# TH.net
KiCad netlist of a schematic drawn in EAGLE
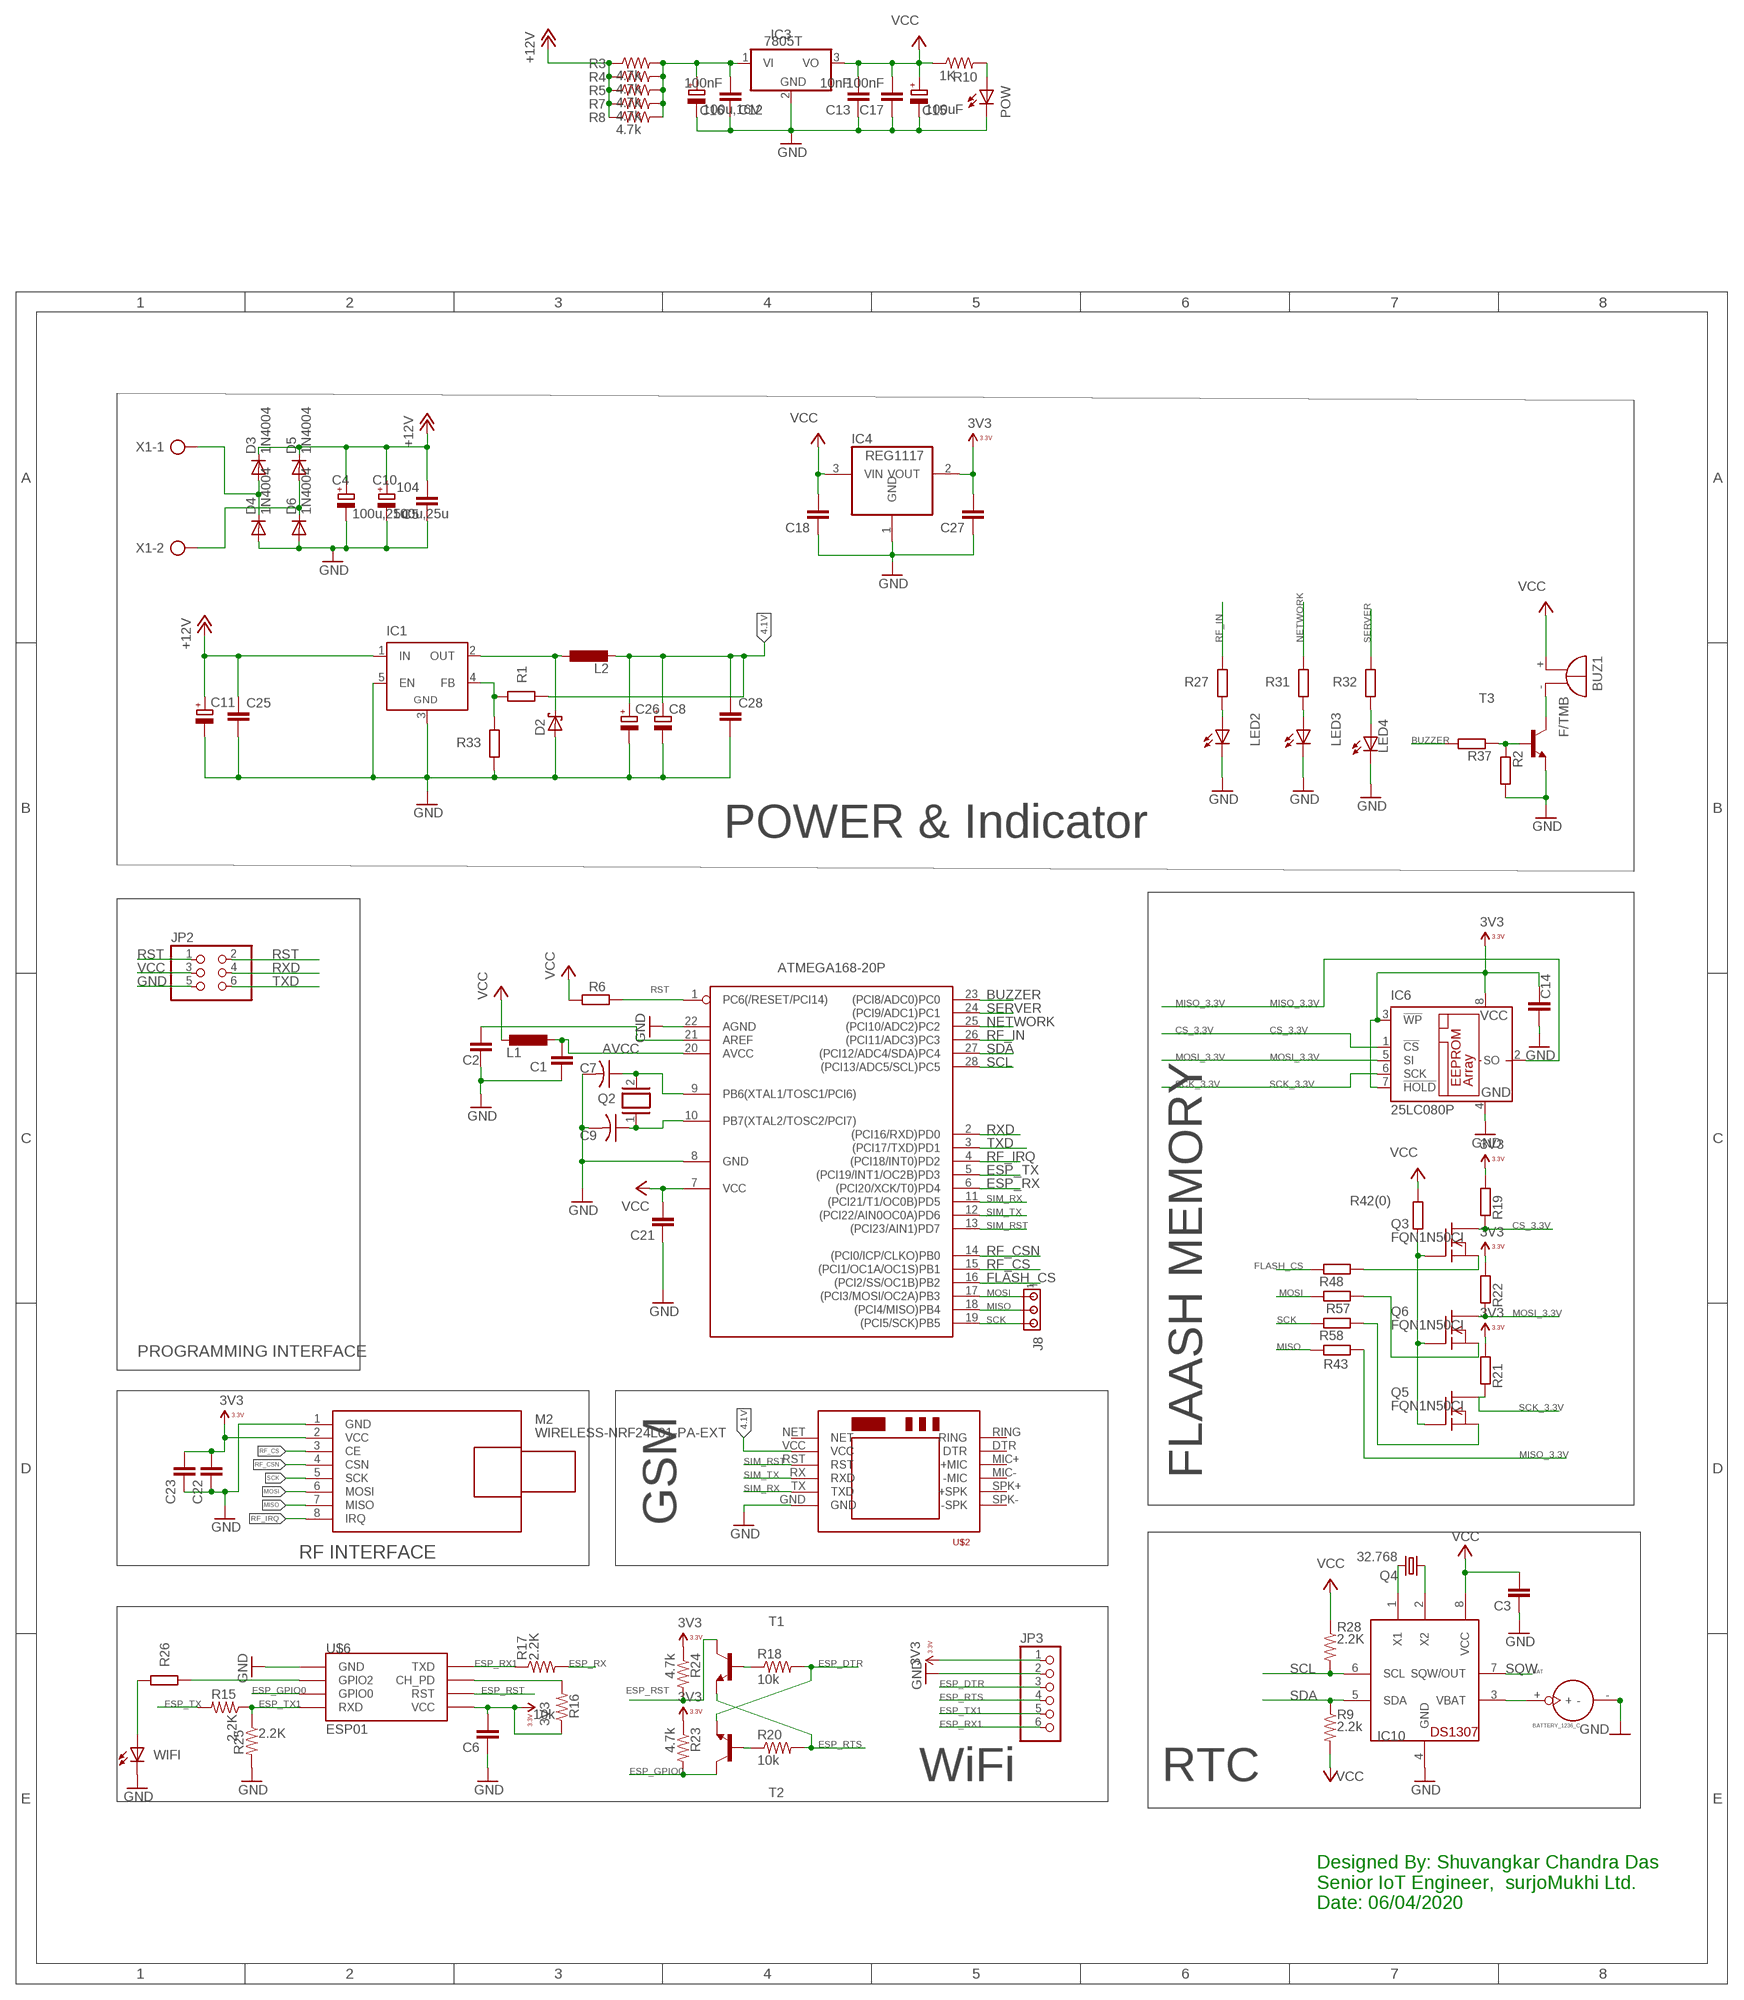
[diagram p0: schematic, sheet 1]

(export (version "E")
  (design (tool "Eeschema 10.0.6"))
  (components
    (comp (ref "BAT")
      (value "BATTERY_1236_C")
      (footprint "eagle-import:BATTERY_1236_C")
      (libsource (lib "eagle-import") (part "BATTERY_1236_C"))
    )
    (comp (ref "BUZ1")
      (value "F/TMB")
      (footprint "eagle-import:F_TMB")
      (libsource (lib "eagle-import") (part "F/TMB"))
    )
    (comp (ref "C1")
      (value "C-EU050-024X044")
      (footprint "eagle-import:C050-024X044")
      (libsource (lib "eagle-import") (part "C-EU050-024X044"))
    )
    (comp (ref "C2")
      (value "C-EU025-025X050")
      (footprint "eagle-import:C025-025X050")
      (libsource (lib "eagle-import") (part "C-EU025-025X050"))
    )
    (comp (ref "C3")
      (value "C-EU050-024X044")
      (footprint "eagle-import:C050-024X044")
      (libsource (lib "eagle-import") (part "C-EU050-024X044"))
    )
    (comp (ref "C4")
      (value "100u,25u")
      (footprint "eagle-import:E3,5-10")
      (libsource (lib "eagle-import") (part "CPOL-EUE3.5-10"))
    )
    (comp (ref "C5")
      (value "104")
      (footprint "eagle-import:C050-024X044")
      (libsource (lib "eagle-import") (part "C-EU050-024X044"))
    )
    (comp (ref "C6")
      (value "C-EU050-024X044")
      (footprint "eagle-import:C050-024X044")
      (libsource (lib "eagle-import") (part "C-EU050-024X044"))
    )
    (comp (ref "C7")
      (value "C-US050-024X044")
      (footprint "eagle-import:C050-024X044")
      (libsource (lib "eagle-import") (part "C-US050-024X044"))
    )
    (comp (ref "C8")
      (value "CPOL-EUE2.5-7")
      (footprint "eagle-import:E2,5-7")
      (libsource (lib "eagle-import") (part "resistor_CPOL-EUE2.5-7"))
    )
    (comp (ref "C9")
      (value "C-US050-024X044")
      (footprint "eagle-import:C050-024X044")
      (libsource (lib "eagle-import") (part "C-US050-024X044"))
    )
    (comp (ref "C10")
      (value "100u,25u")
      (footprint "eagle-import:E3,5-10")
      (libsource (lib "eagle-import") (part "CPOL-EUE3.5-10"))
    )
    (comp (ref "C11")
      (value "CPOL-EUE2.5-7")
      (footprint "eagle-import:E2,5-7")
      (libsource (lib "eagle-import") (part "resistor_CPOL-EUE2.5-7"))
    )
    (comp (ref "C12")
      (value "100nF")
      (footprint "eagle-import:C050-024X044")
      (libsource (lib "eagle-import") (part "C-EU050-024X044"))
    )
    (comp (ref "C13")
      (value "10nF")
      (footprint "eagle-import:C050-024X044")
      (libsource (lib "eagle-import") (part "C-EU050-024X044"))
    )
    (comp (ref "C14")
      (value "C-EU050-024X044")
      (footprint "eagle-import:C050-024X044")
      (libsource (lib "eagle-import") (part "C-EU050-024X044"))
    )
    (comp (ref "C15")
      (value "100uF")
      (footprint "eagle-import:TT2D6")
      (libsource (lib "eagle-import") (part "CPOL-EUTT2D6"))
    )
    (comp (ref "C16")
      (value "100u,16V")
      (footprint "eagle-import:TT2D6")
      (libsource (lib "eagle-import") (part "CPOL-EUTT2D6"))
    )
    (comp (ref "C17")
      (value "100nF")
      (footprint "eagle-import:C050-024X044")
      (libsource (lib "eagle-import") (part "C-EU050-024X044"))
    )
    (comp (ref "C18")
      (value "C-EU050-024X044")
      (footprint "eagle-import:C050-024X044")
      (libsource (lib "eagle-import") (part "C-EU050-024X044"))
    )
    (comp (ref "C21")
      (value "C-EU050-024X044")
      (footprint "eagle-import:C050-024X044")
      (libsource (lib "eagle-import") (part "C-EU050-024X044"))
    )
    (comp (ref "C22")
      (value "C-EU050-024X044")
      (footprint "eagle-import:C050-024X044")
      (libsource (lib "eagle-import") (part "C-EU050-024X044"))
    )
    (comp (ref "C23")
      (value "C-EU050-024X044")
      (footprint "eagle-import:C050-024X044")
      (libsource (lib "eagle-import") (part "C-EU050-024X044"))
    )
    (comp (ref "C25")
      (value "C-EU050-024X044")
      (footprint "eagle-import:C050-024X044")
      (libsource (lib "eagle-import") (part "resistor_C-EU050-024X044"))
    )
    (comp (ref "C26")
      (value "CPOL-EUE2.5-7")
      (footprint "eagle-import:E2,5-7")
      (libsource (lib "eagle-import") (part "resistor_CPOL-EUE2.5-7"))
    )
    (comp (ref "C27")
      (value "C-EU050-024X044")
      (footprint "eagle-import:C050-024X044")
      (libsource (lib "eagle-import") (part "C-EU050-024X044"))
    )
    (comp (ref "C28")
      (value "C-EU050-024X044")
      (footprint "eagle-import:C050-024X044")
      (libsource (lib "eagle-import") (part "resistor_C-EU050-024X044"))
    )
    (comp (ref "D2")
      (value "SCHOTTKY-DIODEDO41")
      (footprint "eagle-import:DO41-10")
      (libsource (lib "eagle-import") (part "SCHOTTKY-DIODEDO41"))
    )
    (comp (ref "D3")
      (value "1N4004")
      (footprint "eagle-import:DO41-10")
      (libsource (lib "eagle-import") (part "1N4004"))
    )
    (comp (ref "D4")
      (value "1N4004")
      (footprint "eagle-import:DO41-10")
      (libsource (lib "eagle-import") (part "1N4004"))
    )
    (comp (ref "D5")
      (value "1N4004")
      (footprint "eagle-import:DO41-10")
      (libsource (lib "eagle-import") (part "1N4004"))
    )
    (comp (ref "D6")
      (value "1N4004")
      (footprint "eagle-import:DO41-10")
      (libsource (lib "eagle-import") (part "1N4004"))
    )
    (comp (ref "IC1")
      (value "LM2596TH")
      (footprint "eagle-import:TO220-52")
      (libsource (lib "eagle-import") (part "LM2596TH"))
    )
    (comp (ref "IC3")
      (value "7805T")
      (footprint "eagle-import:TO220H")
      (libsource (lib "eagle-import") (part "78T05"))
    )
    (comp (ref "IC4")
      (value "REG1117")
      (footprint "eagle-import:SOT223")
      (libsource (lib "eagle-import") (part "REG1117"))
    )
    (comp (ref "IC6")
      (value "25LC080P")
      (footprint "eagle-import:DIL8")
      (fields (field (name "MF") "MICROCHIP") (field (name "MPN") "25LC080/P"))
      (libsource (lib "eagle-import") (part "25PLC080"))
    )
    (comp (ref "IC7")
      (value "ATMEGA168-20P")
      (footprint "eagle-import:DIL28-3")
      (libsource (lib "eagle-import") (part "ATMEGA168P-20"))
    )
    (comp (ref "IC10")
      (value "DS1307")
      (footprint "eagle-import:DIL08")
      (libsource (lib "eagle-import") (part "DS1307"))
    )
    (comp (ref "J8")
      (value "MTA03-100")
      (footprint "eagle-import:10X03MTA")
      (libsource (lib "eagle-import") (part "MTA03-100"))
    )
    (comp (ref "JP2")
      (value "PINHD-2X3")
      (footprint "eagle-import:2X03")
      (libsource (lib "eagle-import") (part "PINHD-2X3"))
    )
    (comp (ref "JP3")
      (value "PINHD-1X6")
      (footprint "eagle-import:1X06")
      (libsource (lib "eagle-import") (part "PINHD-1X6"))
    )
    (comp (ref "L1")
      (value "L-EU0207/15")
      (footprint "eagle-import:0207_15")
      (libsource (lib "eagle-import") (part "L-EU0207/15"))
    )
    (comp (ref "L2")
      (value "L-EU0207/10")
      (footprint "eagle-import:0207_10")
      (libsource (lib "eagle-import") (part "L-EU0207/10"))
    )
    (comp (ref "LED2")
      (value "LED3MM")
      (footprint "eagle-import:LED3MM")
      (libsource (lib "eagle-import") (part "LED3MM"))
    )
    (comp (ref "LED3")
      (value "LED3MM")
      (footprint "eagle-import:LED3MM")
      (libsource (lib "eagle-import") (part "LED3MM"))
    )
    (comp (ref "LED4")
      (value "LED3MM")
      (footprint "eagle-import:LED3MM")
      (libsource (lib "eagle-import") (part "LED3MM"))
    )
    (comp (ref "M2")
      (value "WIRELESS-NRF24L01-PA-EXT")
      (footprint "eagle-import:WIRELESS-NRF24L01-PA-EXT")
      (libsource (lib "eagle-import") (part "WIRELESS-NRF24L01-PA-EXT"))
    )
    (comp (ref "POW")
      (value "LED3MM")
      (footprint "eagle-import:LED3MM")
      (libsource (lib "eagle-import") (part "LED3MM"))
    )
    (comp (ref "Q2")
      (value "XTAL/S")
      (footprint "eagle-import:QS")
      (libsource (lib "eagle-import") (part "XTAL/S"))
    )
    (comp (ref "Q3")
      (value "FQN1N50CI")
      (footprint "eagle-import:TO92-INLINE")
      (libsource (lib "eagle-import") (part "FQN1N50CI"))
    )
    (comp (ref "Q4")
      (value "32.768")
      (footprint "eagle-import:TC38H")
      (libsource (lib "eagle-import") (part "CRYTALTC38H"))
    )
    (comp (ref "Q5")
      (value "FQN1N50CI")
      (footprint "eagle-import:TO92-INLINE")
      (libsource (lib "eagle-import") (part "FQN1N50CI"))
    )
    (comp (ref "Q6")
      (value "FQN1N50CI")
      (footprint "eagle-import:TO92-INLINE")
      (libsource (lib "eagle-import") (part "FQN1N50CI"))
    )
    (comp (ref "R1")
      (value "R-EU_0204/7")
      (footprint "eagle-import:0204_7")
      (libsource (lib "eagle-import") (part "R-EU_0204/7"))
    )
    (comp (ref "R2")
      (value "R-EU_0204/7")
      (footprint "eagle-import:0204_7")
      (libsource (lib "eagle-import") (part "R-EU_0204/7"))
    )
    (comp (ref "R3")
      (value "4.7k")
      (footprint "eagle-import:0204_7")
      (libsource (lib "eagle-import") (part "R-US_0204/7"))
    )
    (comp (ref "R4")
      (value "4.7k")
      (footprint "eagle-import:0204_7")
      (libsource (lib "eagle-import") (part "R-US_0204/7"))
    )
    (comp (ref "R5")
      (value "4.7k")
      (footprint "eagle-import:0204_7")
      (libsource (lib "eagle-import") (part "R-US_0204/7"))
    )
    (comp (ref "R6")
      (value "R-EU_0204/7")
      (footprint "eagle-import:0204_7")
      (libsource (lib "eagle-import") (part "R-EU_0204/7"))
    )
    (comp (ref "R7")
      (value "4.7k")
      (footprint "eagle-import:0204_7")
      (libsource (lib "eagle-import") (part "R-US_0204/7"))
    )
    (comp (ref "R8")
      (value "4.7k")
      (footprint "eagle-import:0204_7")
      (libsource (lib "eagle-import") (part "R-US_0204/7"))
    )
    (comp (ref "R9")
      (value "2.2k")
      (footprint "eagle-import:0204_7")
      (libsource (lib "eagle-import") (part "R-US_0204/7"))
    )
    (comp (ref "R10")
      (value "1K")
      (footprint "eagle-import:0204_7")
      (libsource (lib "eagle-import") (part "R-US_0204/7"))
    )
    (comp (ref "R15")
      (value "2.2K")
      (footprint "eagle-import:0204_7")
      (libsource (lib "eagle-import") (part "R-US_0204/7"))
    )
    (comp (ref "R16")
      (value "10k")
      (footprint "eagle-import:0204_7")
      (libsource (lib "eagle-import") (part "R-US_0204/7"))
    )
    (comp (ref "R17")
      (value "2.2K")
      (footprint "eagle-import:0204_7")
      (libsource (lib "eagle-import") (part "R-US_0204/7"))
    )
    (comp (ref "R18")
      (value "10k")
      (footprint "eagle-import:0204_7")
      (libsource (lib "eagle-import") (part "R-US_0204/7"))
    )
    (comp (ref "R19")
      (value "R-EU_0204/7")
      (footprint "eagle-import:0204_7")
      (libsource (lib "eagle-import") (part "R-EU_0204/7"))
    )
    (comp (ref "R20")
      (value "10k")
      (footprint "eagle-import:0204_7")
      (libsource (lib "eagle-import") (part "R-US_0204/7"))
    )
    (comp (ref "R21")
      (value "R-EU_0204/7")
      (footprint "eagle-import:0204_7")
      (libsource (lib "eagle-import") (part "R-EU_0204/7"))
    )
    (comp (ref "R22")
      (value "R-EU_0204/7")
      (footprint "eagle-import:0204_7")
      (libsource (lib "eagle-import") (part "R-EU_0204/7"))
    )
    (comp (ref "R23")
      (value "4.7k")
      (footprint "eagle-import:0204_7")
      (libsource (lib "eagle-import") (part "R-US_0204/7"))
    )
    (comp (ref "R24")
      (value "4.7k")
      (footprint "eagle-import:0204_7")
      (libsource (lib "eagle-import") (part "R-US_0204/7"))
    )
    (comp (ref "R25")
      (value "2.2K")
      (footprint "eagle-import:0204_7")
      (libsource (lib "eagle-import") (part "R-US_0204/7"))
    )
    (comp (ref "R26")
      (value "R-EU_0204/7")
      (footprint "eagle-import:0204_7")
      (libsource (lib "eagle-import") (part "R-EU_0204/7"))
    )
    (comp (ref "R27")
      (value "R-EU_0207/10")
      (footprint "eagle-import:0207_10")
      (libsource (lib "eagle-import") (part "R-EU_0207/10"))
    )
    (comp (ref "R28")
      (value "2.2K")
      (footprint "eagle-import:0204_7")
      (libsource (lib "eagle-import") (part "R-US_0204/7"))
    )
    (comp (ref "R31")
      (value "R-EU_0207/10")
      (footprint "eagle-import:0207_10")
      (libsource (lib "eagle-import") (part "R-EU_0207/10"))
    )
    (comp (ref "R32")
      (value "R-EU_0207/10")
      (footprint "eagle-import:0207_10")
      (libsource (lib "eagle-import") (part "R-EU_0207/10"))
    )
    (comp (ref "R33")
      (value "R-EU_0204/7")
      (footprint "eagle-import:0204_7")
      (libsource (lib "eagle-import") (part "R-EU_0204/7"))
    )
    (comp (ref "R37")
      (value "R-EU_0204/7")
      (footprint "eagle-import:0204_7")
      (libsource (lib "eagle-import") (part "R-EU_0204/7"))
    )
    (comp (ref "R42(0)")
      (value "R-EU_0207/10")
      (footprint "eagle-import:0207_10")
      (libsource (lib "eagle-import") (part "R-EU_0207/10"))
    )
    (comp (ref "R43")
      (value "R-EU_0207/10")
      (footprint "eagle-import:0207_10")
      (libsource (lib "eagle-import") (part "R-EU_0207/10"))
    )
    (comp (ref "R48")
      (value "R-EU_0207/10")
      (footprint "eagle-import:0207_10")
      (libsource (lib "eagle-import") (part "R-EU_0207/10"))
    )
    (comp (ref "R57")
      (value "R-EU_0207/10")
      (footprint "eagle-import:0207_10")
      (libsource (lib "eagle-import") (part "R-EU_0207/10"))
    )
    (comp (ref "R58")
      (value "R-EU_0207/10")
      (footprint "eagle-import:0207_10")
      (libsource (lib "eagle-import") (part "R-EU_0207/10"))
    )
    (comp (ref "T1")
      (value "BC547-NPN-TO92-CBE")
      (footprint "eagle-import:TO92-CBE")
      (libsource (lib "eagle-import") (part "-NPN-TO92-CBEBC547"))
    )
    (comp (ref "T2")
      (value "BC547-NPN-TO92-CBE")
      (footprint "eagle-import:TO92-CBE")
      (libsource (lib "eagle-import") (part "-NPN-TO92-CBEBC547"))
    )
    (comp (ref "T3")
      (value "BC547A-NPN-TO92-CBE")
      (footprint "eagle-import:TO92-CBE")
      (libsource (lib "eagle-import") (part "-NPN-TO92-CBEBC547A"))
    )
    (comp (ref "U$2")
      (value "SIM800LMODULE")
      (footprint "eagle-import:SIM800LMODULE")
      (libsource (lib "eagle-import") (part "SIM800LMODULE"))
    )
    (comp (ref "U$6")
      (value "ESP01")
      (footprint "eagle-import:ESP01")
      (libsource (lib "eagle-import") (part "ESP01"))
    )
    (comp (ref "WIFI")
      (value "LED3MM")
      (footprint "eagle-import:LED3MM")
      (libsource (lib "eagle-import") (part "LED3MM"))
    )
    (comp (ref "X1")
      (value "AK500/2")
      (footprint "eagle-import:AK500_2")
      (libsource (lib "eagle-import") (part "AK500/2"))
    )
  )
  (nets
    (net (code "1") (name "+12V") (class "Default")
      (node (ref "C10") (pin "+") (pinfunction "+_+") (pintype "passive"))
      (node (ref "C11") (pin "+") (pinfunction "+_+") (pintype "passive"))
      (node (ref "C25") (pin "1") (pinfunction "1_1") (pintype "passive"))
      (node (ref "C4") (pin "+") (pinfunction "+_+") (pintype "passive"))
      (node (ref "C5") (pin "2") (pinfunction "2_2") (pintype "passive"))
      (node (ref "D3") (pin "C") (pinfunction "C_C") (pintype "passive"))
      (node (ref "D5") (pin "C") (pinfunction "C_C") (pintype "passive"))
      (node (ref "IC1") (pin "1") (pinfunction "IN_1") (pintype "input"))
      (node (ref "R3") (pin "1") (pinfunction "1_1") (pintype "passive"))
      (node (ref "R4") (pin "1") (pinfunction "1_1") (pintype "passive"))
      (node (ref "R5") (pin "1") (pinfunction "1_1") (pintype "passive"))
      (node (ref "R7") (pin "1") (pinfunction "1_1") (pintype "passive"))
      (node (ref "R8") (pin "1") (pinfunction "1_1") (pintype "passive"))
    )
    (net (code "2") (name "/AVCC") (class "Default")
      (node (ref "C1") (pin "2") (pinfunction "2_2") (pintype "passive"))
      (node (ref "IC7") (pin "20") (pinfunction "AVCC_20") (pintype "bidirectional"))
      (node (ref "L1") (pin "2") (pinfunction "2_2") (pintype "passive"))
    )
    (net (code "3") (name "/BUZZER") (class "Default")
      (node (ref "IC7") (pin "23") (pinfunction "(PCI8/ADC0)PC0_23") (pintype "bidirectional"))
      (node (ref "R37") (pin "2") (pinfunction "2_2") (pintype "passive"))
    )
    (net (code "4") (name "/CS_3.3V") (class "Default")
      (node (ref "IC6") (pin "1") (pinfunction "~{CS}_1") (pintype "input"))
      (node (ref "Q3") (pin "1") (pinfunction "D_1") (pintype "passive"))
      (node (ref "R19") (pin "1") (pinfunction "1_1") (pintype "passive"))
    )
    (net (code "5") (name "/ESP_DTR") (class "Default")
      (node (ref "JP3") (pin "3") (pinfunction "3_3") (pintype "passive"))
      (node (ref "R18") (pin "2") (pinfunction "2_2") (pintype "passive"))
      (node (ref "T2") (pin "E") (pinfunction "E_E") (pintype "passive"))
    )
    (net (code "6") (name "/ESP_GPIO0") (class "Default")
      (node (ref "R23") (pin "2") (pinfunction "2_2") (pintype "passive"))
      (node (ref "T2") (pin "C") (pinfunction "C_C") (pintype "passive"))
      (node (ref "U$6") (pin "GPIO0") (pinfunction "GPIO0_GPIO0") (pintype "bidirectional"))
    )
    (net (code "7") (name "/ESP_RST") (class "Default")
      (node (ref "R24") (pin "2") (pinfunction "2_2") (pintype "passive"))
      (node (ref "T1") (pin "C") (pinfunction "C_C") (pintype "passive"))
      (node (ref "U$6") (pin "RST") (pinfunction "RST_RST") (pintype "bidirectional"))
    )
    (net (code "8") (name "/ESP_RTS") (class "Default")
      (node (ref "JP3") (pin "4") (pinfunction "4_4") (pintype "passive"))
      (node (ref "R20") (pin "2") (pinfunction "2_2") (pintype "passive"))
      (node (ref "T1") (pin "E") (pinfunction "E_E") (pintype "passive"))
    )
    (net (code "9") (name "/ESP_RX") (class "Default")
      (node (ref "IC7") (pin "6") (pinfunction "(PCI20/XCK/T0)PD4_6") (pintype "bidirectional"))
      (node (ref "R17") (pin "2") (pinfunction "2_2") (pintype "passive"))
    )
    (net (code "10") (name "/ESP_RX1") (class "Default")
      (node (ref "JP3") (pin "6") (pinfunction "6_6") (pintype "passive"))
      (node (ref "R17") (pin "1") (pinfunction "1_1") (pintype "passive"))
      (node (ref "U$6") (pin "TX") (pinfunction "TXD_TX") (pintype "bidirectional"))
    )
    (net (code "11") (name "/ESP_TX") (class "Default")
      (node (ref "IC7") (pin "5") (pinfunction "(PCI19/INT1/OC2B)PD3_5") (pintype "bidirectional"))
      (node (ref "R15") (pin "2") (pinfunction "2_2") (pintype "passive"))
    )
    (net (code "12") (name "/ESP_TX1") (class "Default")
      (node (ref "JP3") (pin "5") (pinfunction "5_5") (pintype "passive"))
      (node (ref "R15") (pin "1") (pinfunction "1_1") (pintype "passive"))
      (node (ref "R25") (pin "1") (pinfunction "1_1") (pintype "passive"))
      (node (ref "U$6") (pin "RX") (pinfunction "RXD_RX") (pintype "bidirectional"))
    )
    (net (code "13") (name "/FLASH_CS") (class "Default")
      (node (ref "IC7") (pin "16") (pinfunction "(PCI2/SS/OC1B)PB2_16") (pintype "bidirectional"))
      (node (ref "R48") (pin "1") (pinfunction "1_1") (pintype "passive"))
    )
    (net (code "14") (name "/MISO_3.3V") (class "Default")
      (node (ref "IC6") (pin "2") (pinfunction "SO_2") (pintype "bidirectional"))
      (node (ref "R43") (pin "1") (pinfunction "1_1") (pintype "passive"))
    )
    (net (code "15") (name "/MOSI_3.3V") (class "Default")
      (node (ref "IC6") (pin "5") (pinfunction "SI_5") (pintype "input"))
      (node (ref "Q6") (pin "1") (pinfunction "D_1") (pintype "passive"))
      (node (ref "R22") (pin "1") (pinfunction "1_1") (pintype "passive"))
    )
    (net (code "16") (name "/NETWORK") (class "Default")
      (node (ref "IC7") (pin "25") (pinfunction "(PCI10/ADC2)PC2_25") (pintype "bidirectional"))
      (node (ref "R31") (pin "2") (pinfunction "2_2") (pintype "passive"))
    )
    (net (code "17") (name "/RF_IN") (class "Default")
      (node (ref "IC7") (pin "26") (pinfunction "(PCI11/ADC3)PC3_26") (pintype "bidirectional"))
      (node (ref "R27") (pin "2") (pinfunction "2_2") (pintype "passive"))
    )
    (net (code "18") (name "/RST") (class "Default")
      (node (ref "IC7") (pin "1") (pinfunction "PC6(/RESET/PCI14)_1") (pintype "bidirectional"))
      (node (ref "JP2") (pin "1") (pinfunction "1_1") (pintype "passive"))
      (node (ref "JP2") (pin "2") (pinfunction "2_2") (pintype "passive"))
      (node (ref "R6") (pin "1") (pinfunction "1_1") (pintype "passive"))
    )
    (net (code "19") (name "/RXD") (class "Default")
      (node (ref "IC7") (pin "2") (pinfunction "(PCI16/RXD)PD0_2") (pintype "bidirectional"))
      (node (ref "JP2") (pin "4") (pinfunction "4_4") (pintype "passive"))
    )
    (net (code "20") (name "/SCK_3.3V") (class "Default")
      (node (ref "IC6") (pin "6") (pinfunction "SCK_6") (pintype "input"))
      (node (ref "Q5") (pin "1") (pinfunction "D_1") (pintype "passive"))
      (node (ref "R21") (pin "1") (pinfunction "1_1") (pintype "passive"))
    )
    (net (code "21") (name "/SCL") (class "Default")
      (node (ref "IC10") (pin "6") (pinfunction "SCL_6") (pintype "bidirectional"))
      (node (ref "IC7") (pin "28") (pinfunction "(PCI13/ADC5/SCL)PC5_28") (pintype "bidirectional"))
      (node (ref "R28") (pin "2") (pinfunction "2_2") (pintype "passive"))
    )
    (net (code "22") (name "/SDA") (class "Default")
      (node (ref "IC10") (pin "5") (pinfunction "SDA_5") (pintype "bidirectional"))
      (node (ref "IC7") (pin "27") (pinfunction "(PCI12/ADC4/SDA)PC4_27") (pintype "bidirectional"))
      (node (ref "R9") (pin "1") (pinfunction "1_1") (pintype "passive"))
    )
    (net (code "23") (name "/SERVER") (class "Default")
      (node (ref "IC7") (pin "24") (pinfunction "(PCI9/ADC1)PC1_24") (pintype "bidirectional"))
      (node (ref "R32") (pin "2") (pinfunction "2_2") (pintype "passive"))
    )
    (net (code "24") (name "/SIM_RST") (class "Default")
      (node (ref "IC7") (pin "13") (pinfunction "(PCI23/AIN1)PD7_13") (pintype "bidirectional"))
      (node (ref "U$2") (pin "RST") (pinfunction "RST_RST") (pintype "bidirectional"))
    )
    (net (code "25") (name "/SIM_RX") (class "Default")
      (node (ref "IC7") (pin "11") (pinfunction "(PCI21/T1/OC0B)PD5_11") (pintype "bidirectional"))
      (node (ref "U$2") (pin "TX") (pinfunction "TXD_TX") (pintype "bidirectional"))
    )
    (net (code "26") (name "/SIM_TX") (class "Default")
      (node (ref "IC7") (pin "12") (pinfunction "(PCI22/AIN0OC0A)PD6_12") (pintype "bidirectional"))
      (node (ref "U$2") (pin "RX") (pinfunction "RXD_RX") (pintype "bidirectional"))
    )
    (net (code "27") (name "/SQW") (class "Default")
      (node (ref "IC10") (pin "7") (pinfunction "SQW/OUT_7") (pintype "bidirectional"))
    )
    (net (code "28") (name "/TXD") (class "Default")
      (node (ref "IC7") (pin "3") (pinfunction "(PCI17/TXD)PD1_3") (pintype "bidirectional"))
      (node (ref "JP2") (pin "6") (pinfunction "6_6") (pintype "passive"))
    )
    (net (code "29") (name "3V3") (class "Default")
      (node (ref "C14") (pin "2") (pinfunction "2_2") (pintype "passive"))
      (node (ref "C22") (pin "2") (pinfunction "2_2") (pintype "passive"))
      (node (ref "C23") (pin "2") (pinfunction "2_2") (pintype "passive"))
      (node (ref "C27") (pin "2") (pinfunction "2_2") (pintype "passive"))
      (node (ref "C6") (pin "2") (pinfunction "2_2") (pintype "passive"))
      (node (ref "IC4") (pin "2") (pinfunction "VOUT_2") (pintype "output"))
      (node (ref "IC6") (pin "3") (pinfunction "~{WP}_3") (pintype "input"))
      (node (ref "IC6") (pin "7") (pinfunction "~{HOLD}_7") (pintype "input"))
      (node (ref "IC6") (pin "8") (pinfunction "VCC_8") (pintype "power_in"))
      (node (ref "JP3") (pin "1") (pinfunction "1_1") (pintype "passive"))
      (node (ref "M2") (pin "2") (pinfunction "VCC_2") (pintype "power_in"))
      (node (ref "R16") (pin "1") (pinfunction "1_1") (pintype "passive"))
      (node (ref "R19") (pin "2") (pinfunction "2_2") (pintype "passive"))
      (node (ref "R21") (pin "2") (pinfunction "2_2") (pintype "passive"))
      (node (ref "R22") (pin "2") (pinfunction "2_2") (pintype "passive"))
      (node (ref "R23") (pin "1") (pinfunction "1_1") (pintype "passive"))
      (node (ref "R24") (pin "1") (pinfunction "1_1") (pintype "passive"))
      (node (ref "U$6") (pin "VCC") (pinfunction "VCC_VCC") (pintype "bidirectional"))
    )
    (net (code "30") (name "4.1V") (class "Default")
      (node (ref "C26") (pin "+") (pinfunction "+_+") (pintype "passive"))
      (node (ref "C28") (pin "1") (pinfunction "1_1") (pintype "passive"))
      (node (ref "C8") (pin "+") (pinfunction "+_+") (pintype "passive"))
      (node (ref "L2") (pin "2") (pinfunction "2_2") (pintype "passive"))
      (node (ref "R1") (pin "2") (pinfunction "2_2") (pintype "passive"))
      (node (ref "U$2") (pin "VCC") (pinfunction "VCC_VCC") (pintype "bidirectional"))
    )
    (net (code "31") (name "GND") (class "Default")
      (node (ref "BAT") (pin "-") (pinfunction "-_-") (pintype "bidirectional"))
      (node (ref "C1") (pin "1") (pinfunction "1_1") (pintype "passive"))
      (node (ref "C10") (pin "-") (pinfunction "-_-") (pintype "passive"))
      (node (ref "C11") (pin "-") (pinfunction "-_-") (pintype "passive"))
      (node (ref "C12") (pin "1") (pinfunction "1_1") (pintype "passive"))
      (node (ref "C13") (pin "1") (pinfunction "1_1") (pintype "passive"))
      (node (ref "C14") (pin "1") (pinfunction "1_1") (pintype "passive"))
      (node (ref "C15") (pin "-") (pinfunction "-_-") (pintype "passive"))
      (node (ref "C16") (pin "-") (pinfunction "-_-") (pintype "passive"))
      (node (ref "C17") (pin "1") (pinfunction "1_1") (pintype "passive"))
      (node (ref "C18") (pin "1") (pinfunction "1_1") (pintype "passive"))
      (node (ref "C2") (pin "1") (pinfunction "1_1") (pintype "passive"))
      (node (ref "C21") (pin "1") (pinfunction "1_1") (pintype "passive"))
      (node (ref "C22") (pin "1") (pinfunction "1_1") (pintype "passive"))
      (node (ref "C23") (pin "1") (pinfunction "1_1") (pintype "passive"))
      (node (ref "C25") (pin "2") (pinfunction "2_2") (pintype "passive"))
      (node (ref "C26") (pin "-") (pinfunction "-_-") (pintype "passive"))
      (node (ref "C27") (pin "1") (pinfunction "1_1") (pintype "passive"))
      (node (ref "C28") (pin "2") (pinfunction "2_2") (pintype "passive"))
      (node (ref "C3") (pin "1") (pinfunction "1_1") (pintype "passive"))
      (node (ref "C4") (pin "-") (pinfunction "-_-") (pintype "passive"))
      (node (ref "C5") (pin "1") (pinfunction "1_1") (pintype "passive"))
      (node (ref "C6") (pin "1") (pinfunction "1_1") (pintype "passive"))
      (node (ref "C7") (pin "2") (pinfunction "2_2") (pintype "passive"))
      (node (ref "C8") (pin "-") (pinfunction "-_-") (pintype "passive"))
      (node (ref "C9") (pin "2") (pinfunction "2_2") (pintype "passive"))
      (node (ref "D2") (pin "A") (pinfunction "A_A") (pintype "passive"))
      (node (ref "D4") (pin "A") (pinfunction "A_A") (pintype "passive"))
      (node (ref "D6") (pin "A") (pinfunction "A_A") (pintype "passive"))
      (node (ref "IC1") (pin "3") (pinfunction "GND_3") (pintype "power_in"))
      (node (ref "IC1") (pin "5") (pinfunction "EN_5") (pintype "input"))
      (node (ref "IC10") (pin "4") (pinfunction "GND_4") (pintype "power_in"))
      (node (ref "IC3") (pin "2") (pinfunction "GND_2") (pintype "passive"))
      (node (ref "IC4") (pin "1") (pinfunction "GND_1") (pintype "power_in"))
      (node (ref "IC6") (pin "4") (pinfunction "GND_4") (pintype "power_in"))
      (node (ref "IC7") (pin "22") (pinfunction "AGND_22") (pintype "bidirectional"))
      (node (ref "IC7") (pin "8") (pinfunction "GND_8") (pintype "bidirectional"))
      (node (ref "JP2") (pin "5") (pinfunction "5_5") (pintype "passive"))
      (node (ref "JP3") (pin "2") (pinfunction "2_2") (pintype "passive"))
      (node (ref "LED2") (pin "K") (pinfunction "C_K") (pintype "passive"))
      (node (ref "LED3") (pin "K") (pinfunction "C_K") (pintype "passive"))
      (node (ref "LED4") (pin "K") (pinfunction "C_K") (pintype "passive"))
      (node (ref "M2") (pin "1") (pinfunction "GND_1") (pintype "power_in"))
      (node (ref "POW") (pin "K") (pinfunction "C_K") (pintype "passive"))
      (node (ref "R2") (pin "2") (pinfunction "2_2") (pintype "passive"))
      (node (ref "R25") (pin "2") (pinfunction "2_2") (pintype "passive"))
      (node (ref "R33") (pin "1") (pinfunction "1_1") (pintype "passive"))
      (node (ref "T3") (pin "E") (pinfunction "E_E") (pintype "passive"))
      (node (ref "U$2") (pin "GND") (pinfunction "GND_GND") (pintype "bidirectional"))
      (node (ref "U$6") (pin "GND") (pinfunction "GND_GND") (pintype "bidirectional"))
      (node (ref "WIFI") (pin "K") (pinfunction "C_K") (pintype "passive"))
    )
    (net (code "32") (name "MISO") (class "Default")
      (node (ref "IC7") (pin "18") (pinfunction "(PCI4/MISO)PB4_18") (pintype "bidirectional"))
      (node (ref "J8") (pin "2") (pinfunction "2_2") (pintype "passive"))
      (node (ref "M2") (pin "7") (pinfunction "MISO_7") (pintype "bidirectional"))
      (node (ref "R43") (pin "2") (pinfunction "2_2") (pintype "passive"))
    )
    (net (code "33") (name "MOSI") (class "Default")
      (node (ref "IC7") (pin "17") (pinfunction "(PCI3/MOSI/OC2A)PB3_17") (pintype "bidirectional"))
      (node (ref "J8") (pin "1") (pinfunction "1_1") (pintype "passive"))
      (node (ref "M2") (pin "6") (pinfunction "MOSI_6") (pintype "bidirectional"))
      (node (ref "Q6") (pin "3") (pinfunction "S_3") (pintype "passive"))
      (node (ref "R57") (pin "1") (pinfunction "1_1") (pintype "passive"))
      (node (ref "R57") (pin "2") (pinfunction "2_2") (pintype "passive"))
    )
    (net (code "34") (name "Net-(BUZ1-Pad-)") (class "Default")
      (node (ref "BUZ1") (pin "-") (pinfunction "-_-") (pintype "passive"))
      (node (ref "T3") (pin "C") (pinfunction "C_C") (pintype "passive"))
    )
    (net (code "35") (name "Net-(IC1-FB)") (class "Default")
      (node (ref "IC1") (pin "4") (pinfunction "FB_4") (pintype "input"))
      (node (ref "R1") (pin "1") (pinfunction "1_1") (pintype "passive"))
      (node (ref "R33") (pin "2") (pinfunction "2_2") (pintype "passive"))
    )
    (net (code "36") (name "Net-(IC1-OUT)") (class "Default")
      (node (ref "D2") (pin "C") (pinfunction "C_C") (pintype "passive"))
      (node (ref "IC1") (pin "2") (pinfunction "OUT_2") (pintype "output"))
      (node (ref "L2") (pin "1") (pinfunction "1_1") (pintype "passive"))
    )
    (net (code "37") (name "Net-(IC3-VI)") (class "Default")
      (node (ref "C12") (pin "2") (pinfunction "2_2") (pintype "passive"))
      (node (ref "C16") (pin "+") (pinfunction "+_+") (pintype "passive"))
      (node (ref "IC3") (pin "1") (pinfunction "VI_1") (pintype "input"))
      (node (ref "R3") (pin "2") (pinfunction "2_2") (pintype "passive"))
      (node (ref "R4") (pin "2") (pinfunction "2_2") (pintype "passive"))
      (node (ref "R5") (pin "2") (pinfunction "2_2") (pintype "passive"))
      (node (ref "R7") (pin "2") (pinfunction "2_2") (pintype "passive"))
      (node (ref "R8") (pin "2") (pinfunction "2_2") (pintype "passive"))
    )
    (net (code "38") (name "Net-(IC7-AREF)") (class "Default")
      (node (ref "C2") (pin "2") (pinfunction "2_2") (pintype "passive"))
      (node (ref "IC7") (pin "21") (pinfunction "AREF_21") (pintype "bidirectional"))
    )
    (net (code "39") (name "Net-(IC7-PB6(XTAL1{slash}TOSC1{slash}PCI6))") (class "Default")
      (node (ref "C7") (pin "1") (pinfunction "1_1") (pintype "passive"))
      (node (ref "IC7") (pin "9") (pinfunction "PB6(XTAL1/TOSC1/PCI6)_9") (pintype "bidirectional"))
      (node (ref "Q2") (pin "2") (pinfunction "2_2") (pintype "passive"))
    )
    (net (code "40") (name "Net-(IC7-PB7(XTAL2{slash}TOSC2{slash}PCI7))") (class "Default")
      (node (ref "C9") (pin "1") (pinfunction "1_1") (pintype "passive"))
      (node (ref "IC7") (pin "10") (pinfunction "PB7(XTAL2/TOSC2/PCI7)_10") (pintype "bidirectional"))
      (node (ref "Q2") (pin "1") (pinfunction "1_1") (pintype "passive"))
    )
    (net (code "41") (name "Net-(IC10-VBAT)") (class "Default")
      (node (ref "BAT") (pin "+") (pinfunction "+_+") (pintype "bidirectional"))
      (node (ref "IC10") (pin "3") (pinfunction "VBAT_3") (pintype "power_in"))
    )
    (net (code "42") (name "Net-(IC10-X1)") (class "Default")
      (node (ref "IC10") (pin "1") (pinfunction "X1_1") (pintype "passive"))
      (node (ref "Q4") (pin "2") (pinfunction "2_2") (pintype "passive"))
    )
    (net (code "43") (name "Net-(IC10-X2)") (class "Default")
      (node (ref "IC10") (pin "2") (pinfunction "X2_2") (pintype "passive"))
      (node (ref "Q4") (pin "1") (pinfunction "1_1") (pintype "passive"))
    )
    (net (code "44") (name "Net-(LED2-PadA)") (class "Default")
      (node (ref "LED2") (pin "A") (pinfunction "A_A") (pintype "passive"))
      (node (ref "R27") (pin "1") (pinfunction "1_1") (pintype "passive"))
    )
    (net (code "45") (name "Net-(LED3-PadA)") (class "Default")
      (node (ref "LED3") (pin "A") (pinfunction "A_A") (pintype "passive"))
      (node (ref "R31") (pin "1") (pinfunction "1_1") (pintype "passive"))
    )
    (net (code "46") (name "Net-(LED4-PadA)") (class "Default")
      (node (ref "LED4") (pin "A") (pinfunction "A_A") (pintype "passive"))
      (node (ref "R32") (pin "1") (pinfunction "1_1") (pintype "passive"))
    )
    (net (code "47") (name "Net-(POW-PadA)") (class "Default")
      (node (ref "POW") (pin "A") (pinfunction "A_A") (pintype "passive"))
      (node (ref "R10") (pin "2") (pinfunction "2_2") (pintype "passive"))
    )
    (net (code "48") (name "Net-(Q3-G)") (class "Default")
      (node (ref "Q3") (pin "2") (pinfunction "G_2") (pintype "passive"))
      (node (ref "Q5") (pin "2") (pinfunction "G_2") (pintype "passive"))
      (node (ref "Q6") (pin "2") (pinfunction "G_2") (pintype "passive"))
      (node (ref "R42(0)") (pin "1") (pinfunction "1_1") (pintype "passive"))
    )
    (net (code "49") (name "Net-(Q3-S)") (class "Default")
      (node (ref "Q3") (pin "3") (pinfunction "S_3") (pintype "passive"))
      (node (ref "R48") (pin "2") (pinfunction "2_2") (pintype "passive"))
    )
    (net (code "50") (name "Net-(R2-Pad1)") (class "Default")
      (node (ref "R2") (pin "1") (pinfunction "1_1") (pintype "passive"))
      (node (ref "R37") (pin "1") (pinfunction "1_1") (pintype "passive"))
      (node (ref "T3") (pin "B") (pinfunction "B_B") (pintype "passive"))
    )
    (net (code "51") (name "Net-(R16-Pad2)") (class "Default")
      (node (ref "R16") (pin "2") (pinfunction "2_2") (pintype "passive"))
      (node (ref "U$6") (pin "CH_PD") (pinfunction "CH_PD_CH_PD") (pintype "bidirectional"))
    )
    (net (code "52") (name "Net-(R18-Pad1)") (class "Default")
      (node (ref "R18") (pin "1") (pinfunction "1_1") (pintype "passive"))
      (node (ref "T1") (pin "B") (pinfunction "B_B") (pintype "passive"))
    )
    (net (code "53") (name "Net-(R20-Pad1)") (class "Default")
      (node (ref "R20") (pin "1") (pinfunction "1_1") (pintype "passive"))
      (node (ref "T2") (pin "B") (pinfunction "B_B") (pintype "passive"))
    )
    (net (code "54") (name "Net-(R26-Pad1)") (class "Default")
      (node (ref "R26") (pin "1") (pinfunction "1_1") (pintype "passive"))
      (node (ref "WIFI") (pin "A") (pinfunction "A_A") (pintype "passive"))
    )
    (net (code "55") (name "Net-(R26-Pad2)") (class "Default")
      (node (ref "R26") (pin "2") (pinfunction "2_2") (pintype "passive"))
      (node (ref "U$6") (pin "GPIO2") (pinfunction "GPIO2_GPIO2") (pintype "bidirectional"))
    )
    (net (code "56") (name "Net-(X1A-KL)") (class "Default")
      (node (ref "D3") (pin "A") (pinfunction "A_A") (pintype "passive"))
      (node (ref "D4") (pin "C") (pinfunction "C_C") (pintype "passive"))
      (node (ref "X1") (pin "1") (pinfunction "KL_1") (pintype "passive"))
    )
    (net (code "57") (name "Net-(X1B-KL)") (class "Default")
      (node (ref "D5") (pin "A") (pinfunction "A_A") (pintype "passive"))
      (node (ref "D6") (pin "C") (pinfunction "C_C") (pintype "passive"))
      (node (ref "X1") (pin "2") (pinfunction "KL_2") (pintype "passive"))
    )
    (net (code "58") (name "RF_CS") (class "Default")
      (node (ref "IC7") (pin "15") (pinfunction "(PCI1/OC1A/OC1S)PB1_15") (pintype "bidirectional"))
      (node (ref "M2") (pin "3") (pinfunction "CE_3") (pintype "bidirectional"))
    )
    (net (code "59") (name "RF_CSN") (class "Default")
      (node (ref "IC7") (pin "14") (pinfunction "(PCI0/ICP/CLKO)PB0_14") (pintype "bidirectional"))
      (node (ref "M2") (pin "4") (pinfunction "CSN_4") (pintype "bidirectional"))
    )
    (net (code "60") (name "RF_IRQ") (class "Default")
      (node (ref "IC7") (pin "4") (pinfunction "(PCI18/INT0)PD2_4") (pintype "bidirectional"))
      (node (ref "M2") (pin "8") (pinfunction "IRQ_8") (pintype "bidirectional"))
    )
    (net (code "61") (name "SCK") (class "Default")
      (node (ref "IC7") (pin "19") (pinfunction "(PCI5/SCK)PB5_19") (pintype "bidirectional"))
      (node (ref "J8") (pin "3") (pinfunction "3_3") (pintype "passive"))
      (node (ref "M2") (pin "5") (pinfunction "SCK_5") (pintype "bidirectional"))
      (node (ref "Q5") (pin "3") (pinfunction "S_3") (pintype "passive"))
      (node (ref "R58") (pin "1") (pinfunction "1_1") (pintype "passive"))
      (node (ref "R58") (pin "2") (pinfunction "2_2") (pintype "passive"))
    )
    (net (code "62") (name "VCC") (class "Default")
      (node (ref "BUZ1") (pin "+") (pinfunction "+_+") (pintype "passive"))
      (node (ref "C13") (pin "2") (pinfunction "2_2") (pintype "passive"))
      (node (ref "C15") (pin "+") (pinfunction "+_+") (pintype "passive"))
      (node (ref "C17") (pin "2") (pinfunction "2_2") (pintype "passive"))
      (node (ref "C18") (pin "2") (pinfunction "2_2") (pintype "passive"))
      (node (ref "C21") (pin "2") (pinfunction "2_2") (pintype "passive"))
      (node (ref "C3") (pin "2") (pinfunction "2_2") (pintype "passive"))
      (node (ref "IC10") (pin "8") (pinfunction "VCC_8") (pintype "power_in"))
      (node (ref "IC3") (pin "3") (pinfunction "VO_3") (pintype "passive"))
      (node (ref "IC4") (pin "3") (pinfunction "VIN_3") (pintype "input"))
      (node (ref "IC7") (pin "7") (pinfunction "VCC_7") (pintype "bidirectional"))
      (node (ref "JP2") (pin "3") (pinfunction "3_3") (pintype "passive"))
      (node (ref "L1") (pin "1") (pinfunction "1_1") (pintype "passive"))
      (node (ref "R10") (pin "1") (pinfunction "1_1") (pintype "passive"))
      (node (ref "R28") (pin "1") (pinfunction "1_1") (pintype "passive"))
      (node (ref "R42(0)") (pin "2") (pinfunction "2_2") (pintype "passive"))
      (node (ref "R6") (pin "2") (pinfunction "2_2") (pintype "passive"))
      (node (ref "R9") (pin "2") (pinfunction "2_2") (pintype "passive"))
    )
    (net (code "63") (name "unconnected-(U$2-+MIC-PadMIC+)") (class "Default")
      (node (ref "U$2") (pin "MIC+") (pinfunction "+MIC_MIC+") (pintype "bidirectional"))
    )
    (net (code "64") (name "unconnected-(U$2-+SPK-PadSPK+)") (class "Default")
      (node (ref "U$2") (pin "SPK+") (pinfunction "+SPK_SPK+") (pintype "bidirectional"))
    )
    (net (code "65") (name "unconnected-(U$2--MIC-PadMIC-)") (class "Default")
      (node (ref "U$2") (pin "MIC-") (pinfunction "-MIC_MIC-") (pintype "bidirectional"))
    )
    (net (code "66") (name "unconnected-(U$2--SPK-PadSPK-)") (class "Default")
      (node (ref "U$2") (pin "SPK-") (pinfunction "-SPK_SPK-") (pintype "bidirectional"))
    )
    (net (code "67") (name "unconnected-(U$2-PadDTR)") (class "Default")
      (node (ref "U$2") (pin "DTR") (pinfunction "DTR_DTR") (pintype "bidirectional"))
    )
    (net (code "68") (name "unconnected-(U$2-PadNET)") (class "Default")
      (node (ref "U$2") (pin "NET") (pinfunction "NET_NET") (pintype "bidirectional"))
    )
    (net (code "69") (name "unconnected-(U$2-PadRING)") (class "Default")
      (node (ref "U$2") (pin "RING") (pinfunction "RING_RING") (pintype "bidirectional"))
    )
  )
)
